# Video_critter_hires_v01.net
KiCad netlist of a schematic drawn in EAGLE
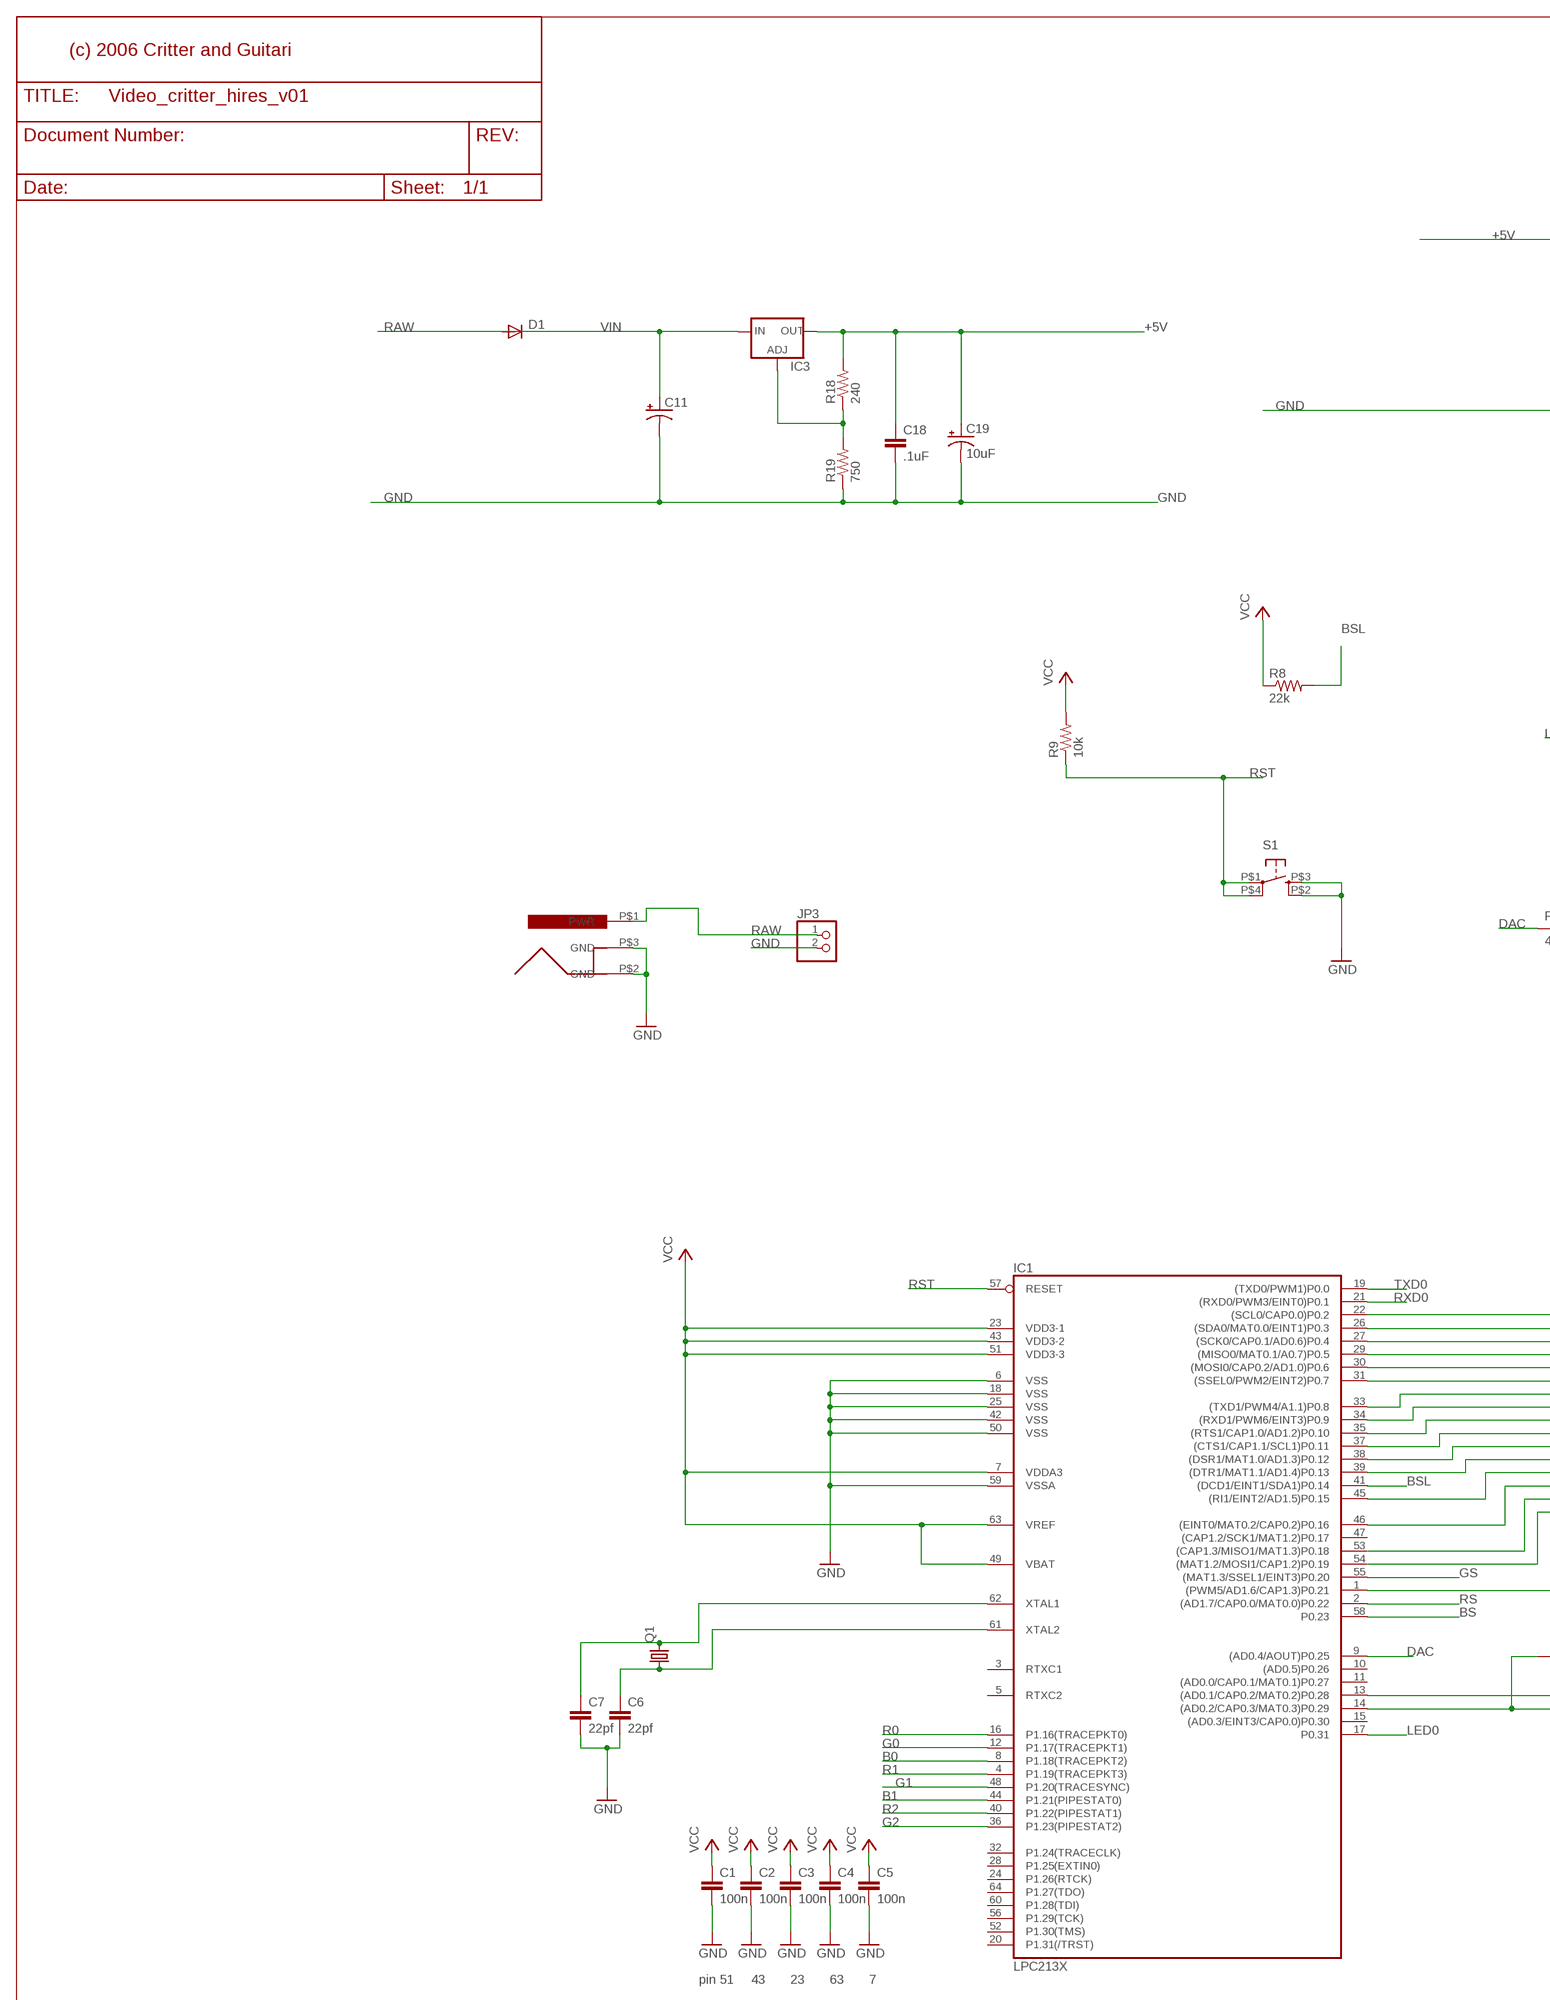
[diagram p0: schematic, sheet 1, part 1 of 2]
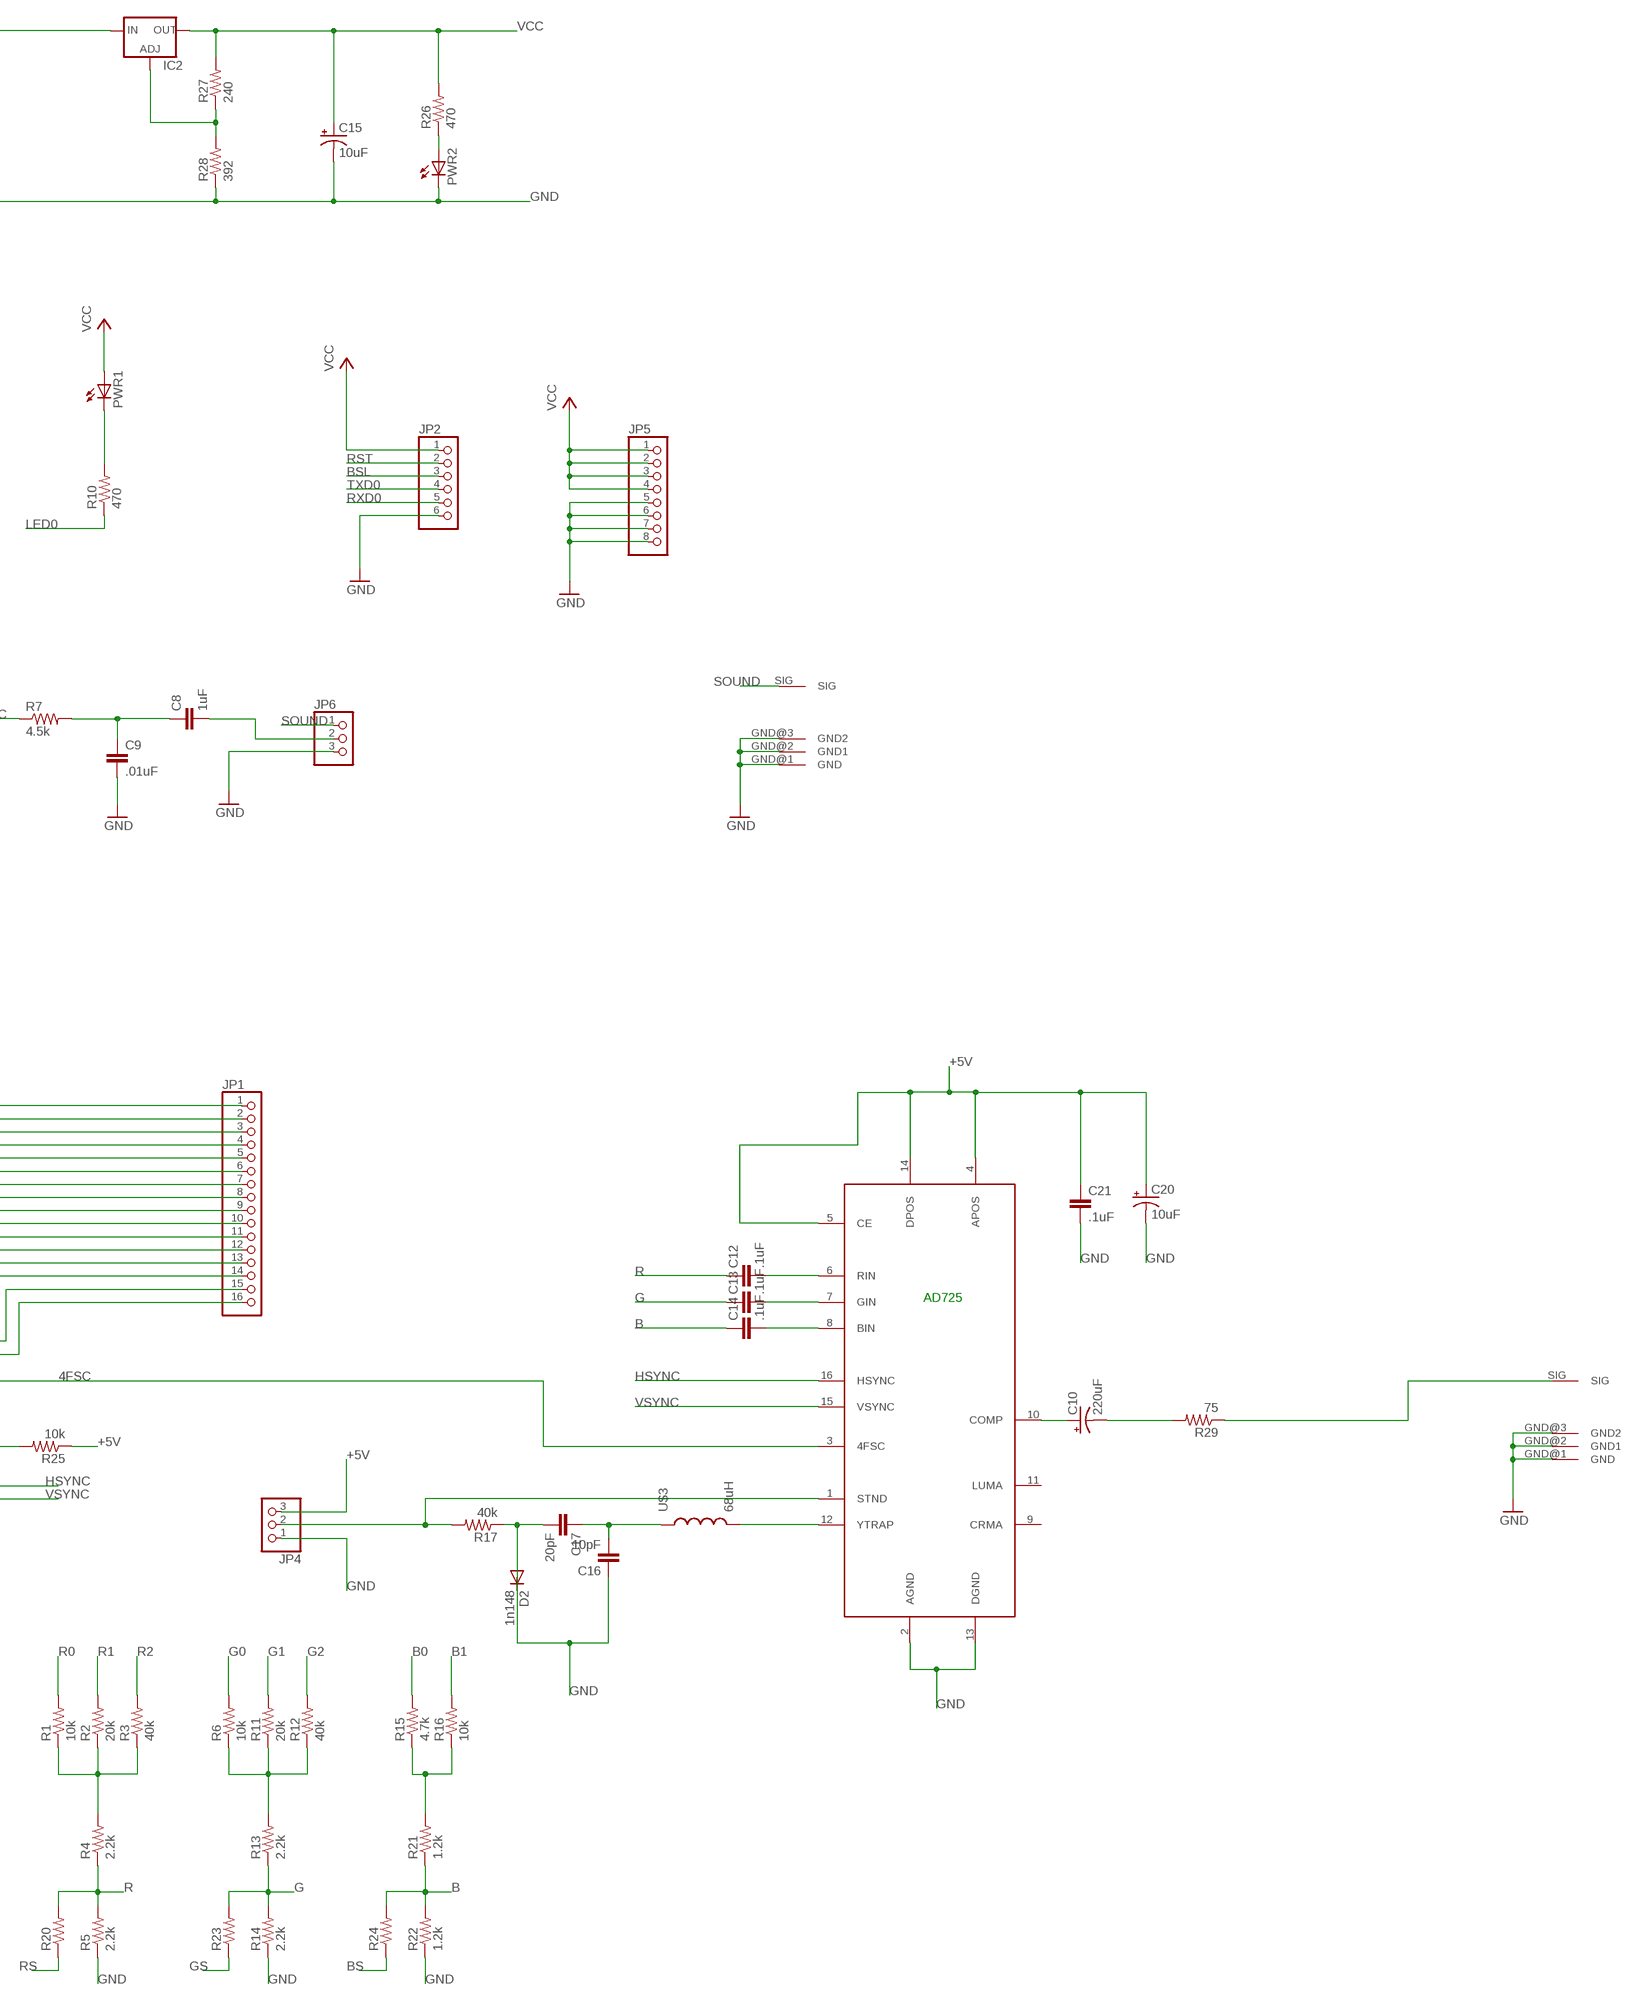
[diagram p1: schematic, sheet 1, part 2 of 2]

(export (version "E")
  (design (tool "Eeschema 10.0.6"))
  (components
    (comp (ref "C1")
      (value "100n")
      (footprint "eagle-import:C0603")
      (libsource (lib "eagle-import") (part "CAP0603"))
    )
    (comp (ref "C2")
      (value "100n")
      (footprint "eagle-import:C0603")
      (libsource (lib "eagle-import") (part "CAP0603"))
    )
    (comp (ref "C3")
      (value "100n")
      (footprint "eagle-import:C0603")
      (libsource (lib "eagle-import") (part "CAP0603"))
    )
    (comp (ref "C4")
      (value "100n")
      (footprint "eagle-import:C0603")
      (libsource (lib "eagle-import") (part "CAP0603"))
    )
    (comp (ref "C5")
      (value "100n")
      (footprint "eagle-import:C0603")
      (libsource (lib "eagle-import") (part "CAP0603"))
    )
    (comp (ref "C6")
      (value "22pf")
      (footprint "eagle-import:C0603")
      (libsource (lib "eagle-import") (part "CAP0603"))
    )
    (comp (ref "C7")
      (value "22pf")
      (footprint "eagle-import:C0603")
      (libsource (lib "eagle-import") (part "CAP0603"))
    )
    (comp (ref "C8")
      (value "1uF")
      (footprint "eagle-import:C0603")
      (libsource (lib "eagle-import") (part "CAP0603"))
    )
    (comp (ref "C9")
      (value ".01uF")
      (footprint "eagle-import:C0603")
      (libsource (lib "eagle-import") (part "CAP0603"))
    )
    (comp (ref "C10")
      (value "220uF")
      (footprint "eagle-import:PANASONIC_D")
      (libsource (lib "eagle-import") (part "CPOL-USD"))
    )
    (comp (ref "C11")
      (value "CPOL-USE3.5-8")
      (footprint "eagle-import:E3,5-8")
      (libsource (lib "eagle-import") (part "CPOL-USE3.5-8"))
    )
    (comp (ref "C12")
      (value ".1uF")
      (footprint "eagle-import:C0603")
      (libsource (lib "eagle-import") (part "CAP0603"))
    )
    (comp (ref "C13")
      (value ".1uF")
      (footprint "eagle-import:C0603")
      (libsource (lib "eagle-import") (part "CAP0603"))
    )
    (comp (ref "C14")
      (value ".1uF")
      (footprint "eagle-import:C0603")
      (libsource (lib "eagle-import") (part "CAP0603"))
    )
    (comp (ref "C15")
      (value "10uF")
      (footprint "eagle-import:CPOL_1206")
      (libsource (lib "eagle-import") (part "CAP_POL1206"))
    )
    (comp (ref "C16")
      (value "10pF")
      (footprint "eagle-import:C0603")
      (libsource (lib "eagle-import") (part "CAP0603"))
    )
    (comp (ref "C17")
      (value "20pF")
      (footprint "eagle-import:C0603")
      (libsource (lib "eagle-import") (part "CAP0603"))
    )
    (comp (ref "C18")
      (value ".1uF")
      (footprint "eagle-import:C0603")
      (libsource (lib "eagle-import") (part "CAP0603"))
    )
    (comp (ref "C19")
      (value "10uF")
      (footprint "eagle-import:CPOL_1206")
      (libsource (lib "eagle-import") (part "CAP_POL1206"))
    )
    (comp (ref "C20")
      (value "10uF")
      (footprint "eagle-import:CPOL_1206")
      (libsource (lib "eagle-import") (part "CAP_POL1206"))
    )
    (comp (ref "C21")
      (value ".1uF")
      (footprint "eagle-import:C0603")
      (libsource (lib "eagle-import") (part "CAP0603"))
    )
    (comp (ref "D1")
      (value "DIODESMB")
      (footprint "eagle-import:SMB")
      (libsource (lib "eagle-import") (part "DIODESMB"))
    )
    (comp (ref "D2")
      (value "1n148")
      (footprint "eagle-import:SOD323-W")
      (libsource (lib "eagle-import") (part "DIODE"))
    )
    (comp (ref "IC1")
      (value "LPC213X")
      (footprint "eagle-import:SQFP-S-10X10-64")
      (libsource (lib "eagle-import") (part "LPC213X"))
    )
    (comp (ref "IC2")
      (value "V_REG_FAN1117SOT223")
      (footprint "eagle-import:SOT223")
      (libsource (lib "eagle-import") (part "V_REG_FAN1117SOT223"))
    )
    (comp (ref "IC3")
      (value "V_REG_FAN1117SOT223")
      (footprint "eagle-import:SOT223")
      (libsource (lib "eagle-import") (part "V_REG_FAN1117SOT223"))
    )
    (comp (ref "JP1")
      (value "PINHD-1X16")
      (footprint "eagle-import:1X16")
      (libsource (lib "eagle-import") (part "PINHD-1X16"))
    )
    (comp (ref "JP2")
      (value "PINHD-1X6")
      (footprint "eagle-import:1X06")
      (libsource (lib "eagle-import") (part "PINHD-1X6"))
    )
    (comp (ref "JP3")
      (value "PINHD-1X2")
      (footprint "eagle-import:1X02")
      (libsource (lib "eagle-import") (part "PINHD-1X2"))
    )
    (comp (ref "JP4")
      (value "PINHD-1X3")
      (footprint "eagle-import:1X03")
      (libsource (lib "eagle-import") (part "PINHD-1X3"))
    )
    (comp (ref "JP5")
      (value "PINHD-1X8")
      (footprint "eagle-import:1X08")
      (libsource (lib "eagle-import") (part "PINHD-1X8"))
    )
    (comp (ref "JP6")
      (value "PINHD-1X3")
      (footprint "eagle-import:1X03")
      (libsource (lib "eagle-import") (part "PINHD-1X3"))
    )
    (comp (ref "PWR1")
      (value "LED1206")
      (footprint "eagle-import:CHIPLED_1206")
      (libsource (lib "eagle-import") (part "LED1206"))
    )
    (comp (ref "PWR2")
      (value "LED1206")
      (footprint "eagle-import:CHIPLED_1206")
      (libsource (lib "eagle-import") (part "LED1206"))
    )
    (comp (ref "Q1")
      (value "CRYSTALSOCKETED")
      (footprint "eagle-import:HC49U-SOCKETED")
      (libsource (lib "eagle-import") (part "CRYSTALSOCKETED"))
    )
    (comp (ref "R1")
      (value "10k")
      (footprint "eagle-import:R0603")
      (libsource (lib "eagle-import") (part "RES0603"))
    )
    (comp (ref "R2")
      (value "20k")
      (footprint "eagle-import:R0603")
      (libsource (lib "eagle-import") (part "RES0603"))
    )
    (comp (ref "R3")
      (value "40k")
      (footprint "eagle-import:R0603")
      (libsource (lib "eagle-import") (part "RES0603"))
    )
    (comp (ref "R4")
      (value "2.2k")
      (footprint "eagle-import:R0603")
      (libsource (lib "eagle-import") (part "RES0603"))
    )
    (comp (ref "R5")
      (value "2.2k")
      (footprint "eagle-import:R0603")
      (libsource (lib "eagle-import") (part "RES0603"))
    )
    (comp (ref "R6")
      (value "10k")
      (footprint "eagle-import:R0603")
      (libsource (lib "eagle-import") (part "RES0603"))
    )
    (comp (ref "R7")
      (value "4.5k")
      (footprint "eagle-import:R0603")
      (libsource (lib "eagle-import") (part "RES0603"))
    )
    (comp (ref "R8")
      (value "22k")
      (footprint "eagle-import:R0603")
      (libsource (lib "eagle-import") (part "RES0603"))
    )
    (comp (ref "R9")
      (value "10k")
      (footprint "eagle-import:R0603")
      (libsource (lib "eagle-import") (part "RES0603"))
    )
    (comp (ref "R10")
      (value "470")
      (footprint "eagle-import:R0603")
      (libsource (lib "eagle-import") (part "RES0603"))
    )
    (comp (ref "R11")
      (value "20k")
      (footprint "eagle-import:R0603")
      (libsource (lib "eagle-import") (part "RES0603"))
    )
    (comp (ref "R12")
      (value "40k")
      (footprint "eagle-import:R0603")
      (libsource (lib "eagle-import") (part "RES0603"))
    )
    (comp (ref "R13")
      (value "2.2k")
      (footprint "eagle-import:R0603")
      (libsource (lib "eagle-import") (part "RES0603"))
    )
    (comp (ref "R14")
      (value "2.2k")
      (footprint "eagle-import:R0603")
      (libsource (lib "eagle-import") (part "RES0603"))
    )
    (comp (ref "R15")
      (value "4.7k")
      (footprint "eagle-import:R0603")
      (libsource (lib "eagle-import") (part "RES0603"))
    )
    (comp (ref "R16")
      (value "10k")
      (footprint "eagle-import:R0603")
      (libsource (lib "eagle-import") (part "RES0603"))
    )
    (comp (ref "R17")
      (value "40k")
      (footprint "eagle-import:R0603")
      (libsource (lib "eagle-import") (part "RES0603"))
    )
    (comp (ref "R18")
      (value "240")
      (footprint "eagle-import:R0603")
      (libsource (lib "eagle-import") (part "RES0603"))
    )
    (comp (ref "R19")
      (value "750")
      (footprint "eagle-import:R0603")
      (libsource (lib "eagle-import") (part "RES0603"))
    )
    (comp (ref "R20")
      (value "RES0603")
      (footprint "eagle-import:R0603")
      (libsource (lib "eagle-import") (part "RES0603"))
    )
    (comp (ref "R21")
      (value "1.2k")
      (footprint "eagle-import:R0603")
      (libsource (lib "eagle-import") (part "RES0603"))
    )
    (comp (ref "R22")
      (value "1.2k")
      (footprint "eagle-import:R0603")
      (libsource (lib "eagle-import") (part "RES0603"))
    )
    (comp (ref "R23")
      (value "RES0603")
      (footprint "eagle-import:R0603")
      (libsource (lib "eagle-import") (part "RES0603"))
    )
    (comp (ref "R24")
      (value "RES0603")
      (footprint "eagle-import:R0603")
      (libsource (lib "eagle-import") (part "RES0603"))
    )
    (comp (ref "R25")
      (value "10k")
      (footprint "eagle-import:R0603")
      (libsource (lib "eagle-import") (part "RES0603"))
    )
    (comp (ref "R26")
      (value "470")
      (footprint "eagle-import:R0603")
      (libsource (lib "eagle-import") (part "RES0603"))
    )
    (comp (ref "R27")
      (value "240")
      (footprint "eagle-import:R0603")
      (libsource (lib "eagle-import") (part "RES0603"))
    )
    (comp (ref "R28")
      (value "392")
      (footprint "eagle-import:R0603")
      (libsource (lib "eagle-import") (part "RES0603"))
    )
    (comp (ref "R29")
      (value "75")
      (footprint "eagle-import:R0603")
      (libsource (lib "eagle-import") (part "RES0603"))
    )
    (comp (ref "S1")
      (value "TAC_SWITCH")
      (footprint "eagle-import:TACTILE_SWITCH_SMD")
      (libsource (lib "eagle-import") (part "TAC_SWITCH"))
    )
    (comp (ref "U$1")
      (value "POWER_JACK")
      (footprint "eagle-import:POWER_JACK")
      (libsource (lib "eagle-import") (part "POWER_JACKTHRU-HOLE"))
    )
    (comp (ref "U$2")
      (value "AD725")
      (footprint "eagle-import:SO16L")
      (libsource (lib "eagle-import") (part "AD725"))
    )
    (comp (ref "U$3")
      (value "68uH")
      (footprint "eagle-import:INDUCTOR_SMALL")
      (libsource (lib "eagle-import") (part "INDUCTORSMALL"))
    )
    (comp (ref "U$5")
      (value "PHONO_PLUG")
      (footprint "eagle-import:PHONO_PCB")
      (libsource (lib "eagle-import") (part "PHONO_PLUG"))
    )
    (comp (ref "U$7")
      (value "PHONO_PLUG")
      (footprint "eagle-import:PHONO_PCB")
      (libsource (lib "eagle-import") (part "PHONO_PLUG"))
    )
  )
  (nets
    (net (code "1") (name "/+5V") (class "Default")
      (node (ref "C18") (pin "1") (pinfunction "1_1") (pintype "passive"))
      (node (ref "C19") (pin "A") (pinfunction "+_A") (pintype "passive"))
      (node (ref "C20") (pin "A") (pinfunction "+_A") (pintype "passive"))
      (node (ref "C21") (pin "1") (pinfunction "1_1") (pintype "passive"))
      (node (ref "IC2") (pin "3") (pinfunction "IN_3") (pintype "input"))
      (node (ref "IC3") (pin "2") (pinfunction "OUT_2") (pintype "passive"))
      (node (ref "JP4") (pin "3") (pinfunction "3_3") (pintype "passive"))
      (node (ref "R18") (pin "2") (pinfunction "2_2") (pintype "passive"))
      (node (ref "R25") (pin "1") (pinfunction "1_1") (pintype "passive"))
      (node (ref "U$2") (pin "14") (pinfunction "DPOS_14") (pintype "bidirectional"))
      (node (ref "U$2") (pin "4") (pinfunction "APOS_4") (pintype "bidirectional"))
      (node (ref "U$2") (pin "5") (pinfunction "CE_5") (pintype "bidirectional"))
    )
    (net (code "2") (name "/4FSC") (class "Default")
      (node (ref "IC1") (pin "1") (pinfunction "(PWM5/AD1.6/CAP1.3)P0.21_1") (pintype "bidirectional"))
      (node (ref "U$2") (pin "3") (pinfunction "4FSC_3") (pintype "bidirectional"))
    )
    (net (code "3") (name "/B") (class "Default")
      (node (ref "C14") (pin "1") (pinfunction "1_1") (pintype "passive"))
      (node (ref "R21") (pin "1") (pinfunction "1_1") (pintype "passive"))
      (node (ref "R22") (pin "2") (pinfunction "2_2") (pintype "passive"))
      (node (ref "R24") (pin "2") (pinfunction "2_2") (pintype "passive"))
    )
    (net (code "4") (name "/B0") (class "Default")
      (node (ref "IC1") (pin "8") (pinfunction "P1.18(TRACEPKT2)_8") (pintype "bidirectional"))
      (node (ref "R15") (pin "2") (pinfunction "2_2") (pintype "passive"))
    )
    (net (code "5") (name "/B1") (class "Default")
      (node (ref "IC1") (pin "44") (pinfunction "P1.21(PIPESTAT0)_44") (pintype "bidirectional"))
      (node (ref "R16") (pin "2") (pinfunction "2_2") (pintype "passive"))
    )
    (net (code "6") (name "/BS") (class "Default")
      (node (ref "IC1") (pin "58") (pinfunction "P0.23_58") (pintype "bidirectional"))
      (node (ref "R24") (pin "1") (pinfunction "1_1") (pintype "passive"))
    )
    (net (code "7") (name "/BSL") (class "Default")
      (node (ref "IC1") (pin "41") (pinfunction "(DCD1/EINT1/SDA1)P0.14_41") (pintype "bidirectional"))
      (node (ref "JP2") (pin "3") (pinfunction "3_3") (pintype "passive"))
      (node (ref "R8") (pin "2") (pinfunction "2_2") (pintype "passive"))
    )
    (net (code "8") (name "/DAC") (class "Default")
      (node (ref "IC1") (pin "9") (pinfunction "(AD0.4/AOUT)P0.25_9") (pintype "bidirectional"))
      (node (ref "R7") (pin "1") (pinfunction "1_1") (pintype "passive"))
    )
    (net (code "9") (name "/G") (class "Default")
      (node (ref "C13") (pin "1") (pinfunction "1_1") (pintype "passive"))
      (node (ref "R13") (pin "1") (pinfunction "1_1") (pintype "passive"))
      (node (ref "R14") (pin "2") (pinfunction "2_2") (pintype "passive"))
      (node (ref "R23") (pin "2") (pinfunction "2_2") (pintype "passive"))
    )
    (net (code "10") (name "/G0") (class "Default")
      (node (ref "IC1") (pin "12") (pinfunction "P1.17(TRACEPKT1)_12") (pintype "bidirectional"))
      (node (ref "R6") (pin "2") (pinfunction "2_2") (pintype "passive"))
    )
    (net (code "11") (name "/G1") (class "Default")
      (node (ref "IC1") (pin "48") (pinfunction "P1.20(TRACESYNC)_48") (pintype "bidirectional"))
      (node (ref "R11") (pin "2") (pinfunction "2_2") (pintype "passive"))
    )
    (net (code "12") (name "/G2") (class "Default")
      (node (ref "IC1") (pin "36") (pinfunction "P1.23(PIPESTAT2)_36") (pintype "bidirectional"))
      (node (ref "R12") (pin "2") (pinfunction "2_2") (pintype "passive"))
    )
    (net (code "13") (name "/GS") (class "Default")
      (node (ref "IC1") (pin "55") (pinfunction "(MAT1.3/SSEL1/EINT3)P0.20_55") (pintype "bidirectional"))
      (node (ref "R23") (pin "1") (pinfunction "1_1") (pintype "passive"))
    )
    (net (code "14") (name "/HSYNC") (class "Default")
      (node (ref "IC1") (pin "13") (pinfunction "(AD0.1/CAP0.2/MAT0.2)P0.28_13") (pintype "bidirectional"))
      (node (ref "U$2") (pin "16") (pinfunction "HSYNC_16") (pintype "bidirectional"))
    )
    (net (code "15") (name "/LED0") (class "Default")
      (node (ref "IC1") (pin "17") (pinfunction "P0.31_17") (pintype "output"))
      (node (ref "R10") (pin "1") (pinfunction "1_1") (pintype "passive"))
    )
    (net (code "16") (name "/R") (class "Default")
      (node (ref "C12") (pin "1") (pinfunction "1_1") (pintype "passive"))
      (node (ref "R20") (pin "2") (pinfunction "2_2") (pintype "passive"))
      (node (ref "R4") (pin "1") (pinfunction "1_1") (pintype "passive"))
      (node (ref "R5") (pin "2") (pinfunction "2_2") (pintype "passive"))
    )
    (net (code "17") (name "/R0") (class "Default")
      (node (ref "IC1") (pin "16") (pinfunction "P1.16(TRACEPKT0)_16") (pintype "bidirectional"))
      (node (ref "R1") (pin "2") (pinfunction "2_2") (pintype "passive"))
    )
    (net (code "18") (name "/R1") (class "Default")
      (node (ref "IC1") (pin "4") (pinfunction "P1.19(TRACEPKT3)_4") (pintype "bidirectional"))
      (node (ref "R2") (pin "2") (pinfunction "2_2") (pintype "passive"))
    )
    (net (code "19") (name "/R2") (class "Default")
      (node (ref "IC1") (pin "40") (pinfunction "P1.22(PIPESTAT1)_40") (pintype "bidirectional"))
      (node (ref "R3") (pin "2") (pinfunction "2_2") (pintype "passive"))
    )
    (net (code "20") (name "/RAW") (class "Default")
      (node (ref "D1") (pin "1") (pinfunction "C_1") (pintype "passive"))
      (node (ref "JP3") (pin "1") (pinfunction "1_1") (pintype "passive"))
      (node (ref "U$1") (pin "P$1") (pinfunction "PWR_P$1") (pintype "bidirectional"))
    )
    (net (code "21") (name "/RS") (class "Default")
      (node (ref "IC1") (pin "2") (pinfunction "(AD1.7/CAP0.0/MAT0.0)P0.22_2") (pintype "bidirectional"))
      (node (ref "R20") (pin "1") (pinfunction "1_1") (pintype "passive"))
    )
    (net (code "22") (name "/RST") (class "Default")
      (node (ref "IC1") (pin "57") (pinfunction "RESET_57") (pintype "input"))
      (node (ref "JP2") (pin "2") (pinfunction "2_2") (pintype "passive"))
      (node (ref "R9") (pin "1") (pinfunction "1_1") (pintype "passive"))
      (node (ref "S1") (pin "P$1") (pinfunction "P_P$1") (pintype "passive"))
      (node (ref "S1") (pin "P$4") (pinfunction "P1_P$4") (pintype "passive"))
    )
    (net (code "23") (name "/RXD0") (class "Default")
      (node (ref "IC1") (pin "21") (pinfunction "(RXD0/PWM3/EINT0)P0.1_21") (pintype "bidirectional"))
      (node (ref "JP2") (pin "5") (pinfunction "5_5") (pintype "passive"))
    )
    (net (code "24") (name "/SOUND") (class "Default")
      (node (ref "JP6") (pin "1") (pinfunction "1_1") (pintype "passive"))
      (node (ref "U$5") (pin "SIG") (pinfunction "SIG_SIG") (pintype "bidirectional"))
    )
    (net (code "25") (name "/TXD0") (class "Default")
      (node (ref "IC1") (pin "19") (pinfunction "(TXD0/PWM1)P0.0_19") (pintype "bidirectional"))
      (node (ref "JP2") (pin "4") (pinfunction "4_4") (pintype "passive"))
    )
    (net (code "26") (name "/VIN") (class "Default")
      (node (ref "C11") (pin "+") (pinfunction "+_+") (pintype "passive"))
      (node (ref "D1") (pin "2") (pinfunction "A_2") (pintype "passive"))
      (node (ref "IC3") (pin "3") (pinfunction "IN_3") (pintype "input"))
    )
    (net (code "27") (name "/VSYNC") (class "Default")
      (node (ref "IC1") (pin "14") (pinfunction "(AD0.2/CAP0.3/MAT0.3)P0.29_14") (pintype "bidirectional"))
      (node (ref "R25") (pin "2") (pinfunction "2_2") (pintype "passive"))
      (node (ref "U$2") (pin "15") (pinfunction "VSYNC_15") (pintype "bidirectional"))
    )
    (net (code "28") (name "GND") (class "Default")
      (node (ref "C1") (pin "2") (pinfunction "2_2") (pintype "passive"))
      (node (ref "C11") (pin "-") (pinfunction "-_-") (pintype "passive"))
      (node (ref "C15") (pin "C") (pinfunction "-_C") (pintype "passive"))
      (node (ref "C16") (pin "1") (pinfunction "1_1") (pintype "passive"))
      (node (ref "C18") (pin "2") (pinfunction "2_2") (pintype "passive"))
      (node (ref "C19") (pin "C") (pinfunction "-_C") (pintype "passive"))
      (node (ref "C2") (pin "2") (pinfunction "2_2") (pintype "passive"))
      (node (ref "C20") (pin "C") (pinfunction "-_C") (pintype "passive"))
      (node (ref "C21") (pin "2") (pinfunction "2_2") (pintype "passive"))
      (node (ref "C3") (pin "2") (pinfunction "2_2") (pintype "passive"))
      (node (ref "C4") (pin "2") (pinfunction "2_2") (pintype "passive"))
      (node (ref "C5") (pin "2") (pinfunction "2_2") (pintype "passive"))
      (node (ref "C6") (pin "2") (pinfunction "2_2") (pintype "passive"))
      (node (ref "C7") (pin "2") (pinfunction "2_2") (pintype "passive"))
      (node (ref "C9") (pin "2") (pinfunction "2_2") (pintype "passive"))
      (node (ref "D2") (pin "A") (pinfunction "A_A") (pintype "passive"))
      (node (ref "IC1") (pin "18") (pinfunction "VSS_18") (pintype "power_in"))
      (node (ref "IC1") (pin "25") (pinfunction "VSS_25") (pintype "power_in"))
      (node (ref "IC1") (pin "42") (pinfunction "VSS_42") (pintype "power_in"))
      (node (ref "IC1") (pin "50") (pinfunction "VSS_50") (pintype "power_in"))
      (node (ref "IC1") (pin "59") (pinfunction "VSSA_59") (pintype "power_in"))
      (node (ref "IC1") (pin "6") (pinfunction "VSS_6") (pintype "power_in"))
      (node (ref "JP2") (pin "6") (pinfunction "6_6") (pintype "passive"))
      (node (ref "JP3") (pin "2") (pinfunction "2_2") (pintype "passive"))
      (node (ref "JP4") (pin "1") (pinfunction "1_1") (pintype "passive"))
      (node (ref "JP5") (pin "5") (pinfunction "5_5") (pintype "passive"))
      (node (ref "JP5") (pin "6") (pinfunction "6_6") (pintype "passive"))
      (node (ref "JP5") (pin "7") (pinfunction "7_7") (pintype "passive"))
      (node (ref "JP5") (pin "8") (pinfunction "8_8") (pintype "passive"))
      (node (ref "JP6") (pin "3") (pinfunction "3_3") (pintype "passive"))
      (node (ref "PWR2") (pin "C") (pinfunction "C_C") (pintype "passive"))
      (node (ref "R14") (pin "1") (pinfunction "1_1") (pintype "passive"))
      (node (ref "R19") (pin "1") (pinfunction "1_1") (pintype "passive"))
      (node (ref "R22") (pin "1") (pinfunction "1_1") (pintype "passive"))
      (node (ref "R28") (pin "1") (pinfunction "1_1") (pintype "passive"))
      (node (ref "R5") (pin "1") (pinfunction "1_1") (pintype "passive"))
      (node (ref "S1") (pin "P$2") (pinfunction "S1_P$2") (pintype "passive"))
      (node (ref "S1") (pin "P$3") (pinfunction "S_P$3") (pintype "passive"))
      (node (ref "U$1") (pin "P$2") (pinfunction "GND_P$2") (pintype "bidirectional"))
      (node (ref "U$1") (pin "P$3") (pinfunction "GND_P$3") (pintype "bidirectional"))
      (node (ref "U$2") (pin "13") (pinfunction "DGND_13") (pintype "bidirectional"))
      (node (ref "U$2") (pin "2") (pinfunction "AGND_2") (pintype "bidirectional"))
      (node (ref "U$5") (pin "GND@1") (pinfunction "GND_GND@1") (pintype "bidirectional"))
      (node (ref "U$5") (pin "GND@2") (pinfunction "GND1_GND@2") (pintype "bidirectional"))
      (node (ref "U$5") (pin "GND@3") (pinfunction "GND2_GND@3") (pintype "bidirectional"))
      (node (ref "U$7") (pin "GND@1") (pinfunction "GND_GND@1") (pintype "bidirectional"))
      (node (ref "U$7") (pin "GND@2") (pinfunction "GND1_GND@2") (pintype "bidirectional"))
      (node (ref "U$7") (pin "GND@3") (pinfunction "GND2_GND@3") (pintype "bidirectional"))
    )
    (net (code "29") (name "Net-(C8-Pad1)") (class "Default")
      (node (ref "C8") (pin "1") (pinfunction "1_1") (pintype "passive"))
      (node (ref "C9") (pin "1") (pinfunction "1_1") (pintype "passive"))
      (node (ref "R7") (pin "2") (pinfunction "2_2") (pintype "passive"))
    )
    (net (code "30") (name "Net-(C8-Pad2)") (class "Default")
      (node (ref "C8") (pin "2") (pinfunction "2_2") (pintype "passive"))
      (node (ref "JP6") (pin "2") (pinfunction "2_2") (pintype "passive"))
    )
    (net (code "31") (name "Net-(C10-Pad-)") (class "Default")
      (node (ref "C10") (pin "-") (pinfunction "-_-") (pintype "passive"))
      (node (ref "R29") (pin "2") (pinfunction "2_2") (pintype "passive"))
    )
    (net (code "32") (name "Net-(C17-Pad2)") (class "Default")
      (node (ref "C17") (pin "2") (pinfunction "2_2") (pintype "passive"))
      (node (ref "D2") (pin "C") (pinfunction "C_C") (pintype "passive"))
      (node (ref "R17") (pin "1") (pinfunction "1_1") (pintype "passive"))
    )
    (net (code "33") (name "Net-(IC1-(CAP1.3{slash}MISO1{slash}MAT1.3)P0.18)") (class "Default")
      (node (ref "IC1") (pin "53") (pinfunction "(CAP1.3/MISO1/MAT1.3)P0.18_53") (pintype "bidirectional"))
      (node (ref "JP1") (pin "15") (pinfunction "15_15") (pintype "passive"))
    )
    (net (code "34") (name "Net-(IC1-(CTS1{slash}CAP1.1{slash}SCL1)P0.11)") (class "Default")
      (node (ref "IC1") (pin "37") (pinfunction "(CTS1/CAP1.1/SCL1)P0.11_37") (pintype "bidirectional"))
      (node (ref "JP1") (pin "10") (pinfunction "10_10") (pintype "passive"))
    )
    (net (code "35") (name "Net-(IC1-(DSR1{slash}MAT1.0{slash}AD1.3)P0.12)") (class "Default")
      (node (ref "IC1") (pin "38") (pinfunction "(DSR1/MAT1.0/AD1.3)P0.12_38") (pintype "bidirectional"))
      (node (ref "JP1") (pin "11") (pinfunction "11_11") (pintype "passive"))
    )
    (net (code "36") (name "Net-(IC1-(DTR1{slash}MAT1.1{slash}AD1.4)P0.13)") (class "Default")
      (node (ref "IC1") (pin "39") (pinfunction "(DTR1/MAT1.1/AD1.4)P0.13_39") (pintype "bidirectional"))
      (node (ref "JP1") (pin "12") (pinfunction "12_12") (pintype "passive"))
    )
    (net (code "37") (name "Net-(IC1-(EINT0{slash}MAT0.2{slash}CAP0.2)P0.16)") (class "Default")
      (node (ref "IC1") (pin "46") (pinfunction "(EINT0/MAT0.2/CAP0.2)P0.16_46") (pintype "bidirectional"))
      (node (ref "JP1") (pin "14") (pinfunction "14_14") (pintype "passive"))
    )
    (net (code "38") (name "Net-(IC1-(MAT1.2{slash}MOSI1{slash}CAP1.2)P0.19)") (class "Default")
      (node (ref "IC1") (pin "54") (pinfunction "(MAT1.2/MOSI1/CAP1.2)P0.19_54") (pintype "bidirectional"))
      (node (ref "JP1") (pin "16") (pinfunction "16_16") (pintype "passive"))
    )
    (net (code "39") (name "Net-(IC1-(MISO0{slash}MAT0.1{slash}A0.7)P0.5)") (class "Default")
      (node (ref "IC1") (pin "29") (pinfunction "(MISO0/MAT0.1/A0.7)P0.5_29") (pintype "bidirectional"))
      (node (ref "JP1") (pin "4") (pinfunction "4_4") (pintype "passive"))
    )
    (net (code "40") (name "Net-(IC1-(MOSI0{slash}CAP0.2{slash}AD1.0)P0.6)") (class "Default")
      (node (ref "IC1") (pin "30") (pinfunction "(MOSI0/CAP0.2/AD1.0)P0.6_30") (pintype "bidirectional"))
      (node (ref "JP1") (pin "5") (pinfunction "5_5") (pintype "passive"))
    )
    (net (code "41") (name "Net-(IC1-(RI1{slash}EINT2{slash}AD1.5)P0.15)") (class "Default")
      (node (ref "IC1") (pin "45") (pinfunction "(RI1/EINT2/AD1.5)P0.15_45") (pintype "bidirectional"))
      (node (ref "JP1") (pin "13") (pinfunction "13_13") (pintype "passive"))
    )
    (net (code "42") (name "Net-(IC1-(RTS1{slash}CAP1.0{slash}AD1.2)P0.10)") (class "Default")
      (node (ref "IC1") (pin "35") (pinfunction "(RTS1/CAP1.0/AD1.2)P0.10_35") (pintype "bidirectional"))
      (node (ref "JP1") (pin "9") (pinfunction "9_9") (pintype "passive"))
    )
    (net (code "43") (name "Net-(IC1-(RXD1{slash}PWM6{slash}EINT3)P0.9)") (class "Default")
      (node (ref "IC1") (pin "34") (pinfunction "(RXD1/PWM6/EINT3)P0.9_34") (pintype "bidirectional"))
      (node (ref "JP1") (pin "8") (pinfunction "8_8") (pintype "passive"))
    )
    (net (code "44") (name "Net-(IC1-(SCK0{slash}CAP0.1{slash}AD0.6)P0.4)") (class "Default")
      (node (ref "IC1") (pin "27") (pinfunction "(SCK0/CAP0.1/AD0.6)P0.4_27") (pintype "bidirectional"))
      (node (ref "JP1") (pin "3") (pinfunction "3_3") (pintype "passive"))
    )
    (net (code "45") (name "Net-(IC1-(SCL0{slash}CAP0.0)P0.2)") (class "Default")
      (node (ref "IC1") (pin "22") (pinfunction "(SCL0/CAP0.0)P0.2_22") (pintype "bidirectional"))
      (node (ref "JP1") (pin "1") (pinfunction "1_1") (pintype "passive"))
    )
    (net (code "46") (name "Net-(IC1-(SDA0{slash}MAT0.0{slash}EINT1)P0.3)") (class "Default")
      (node (ref "IC1") (pin "26") (pinfunction "(SDA0/MAT0.0/EINT1)P0.3_26") (pintype "bidirectional"))
      (node (ref "JP1") (pin "2") (pinfunction "2_2") (pintype "passive"))
    )
    (net (code "47") (name "Net-(IC1-(SSEL0{slash}PWM2{slash}EINT2)P0.7)") (class "Default")
      (node (ref "IC1") (pin "31") (pinfunction "(SSEL0/PWM2/EINT2)P0.7_31") (pintype "bidirectional"))
      (node (ref "JP1") (pin "6") (pinfunction "6_6") (pintype "passive"))
    )
    (net (code "48") (name "Net-(IC1-(TXD1{slash}PWM4{slash}A1.1)P0.8)") (class "Default")
      (node (ref "IC1") (pin "33") (pinfunction "(TXD1/PWM4/A1.1)P0.8_33") (pintype "bidirectional"))
      (node (ref "JP1") (pin "7") (pinfunction "7_7") (pintype "passive"))
    )
    (net (code "49") (name "Net-(IC1-XTAL1)") (class "Default")
      (node (ref "C7") (pin "1") (pinfunction "1_1") (pintype "passive"))
      (node (ref "IC1") (pin "62") (pinfunction "XTAL1_62") (pintype "input"))
      (node (ref "Q1") (pin "2") (pinfunction "2_2") (pintype "passive"))
    )
    (net (code "50") (name "Net-(IC1-XTAL2)") (class "Default")
      (node (ref "C6") (pin "1") (pinfunction "1_1") (pintype "passive"))
      (node (ref "IC1") (pin "61") (pinfunction "XTAL2_61") (pintype "output"))
      (node (ref "Q1") (pin "1") (pinfunction "1_1") (pintype "passive"))
    )
    (net (code "51") (name "Net-(IC2-ADJ)") (class "Default")
      (node (ref "IC2") (pin "1") (pinfunction "ADJ_1") (pintype "input"))
      (node (ref "R27") (pin "1") (pinfunction "1_1") (pintype "passive"))
      (node (ref "R28") (pin "2") (pinfunction "2_2") (pintype "passive"))
    )
    (net (code "52") (name "Net-(IC3-ADJ)") (class "Default")
      (node (ref "IC3") (pin "1") (pinfunction "ADJ_1") (pintype "input"))
      (node (ref "R18") (pin "1") (pinfunction "1_1") (pintype "passive"))
      (node (ref "R19") (pin "2") (pinfunction "2_2") (pintype "passive"))
    )
    (net (code "53") (name "Net-(PWR1-PadC)") (class "Default")
      (node (ref "PWR1") (pin "C") (pinfunction "C_C") (pintype "passive"))
      (node (ref "R10") (pin "2") (pinfunction "2_2") (pintype "passive"))
    )
    (net (code "54") (name "Net-(PWR2-PadA)") (class "Default")
      (node (ref "PWR2") (pin "A") (pinfunction "A_A") (pintype "passive"))
      (node (ref "R26") (pin "1") (pinfunction "1_1") (pintype "passive"))
    )
    (net (code "55") (name "Net-(R1-Pad1)") (class "Default")
      (node (ref "R1") (pin "1") (pinfunction "1_1") (pintype "passive"))
      (node (ref "R2") (pin "1") (pinfunction "1_1") (pintype "passive"))
      (node (ref "R3") (pin "1") (pinfunction "1_1") (pintype "passive"))
      (node (ref "R4") (pin "2") (pinfunction "2_2") (pintype "passive"))
    )
    (net (code "56") (name "Net-(R11-Pad1)") (class "Default")
      (node (ref "R11") (pin "1") (pinfunction "1_1") (pintype "passive"))
      (node (ref "R12") (pin "1") (pinfunction "1_1") (pintype "passive"))
      (node (ref "R13") (pin "2") (pinfunction "2_2") (pintype "passive"))
      (node (ref "R6") (pin "1") (pinfunction "1_1") (pintype "passive"))
    )
    (net (code "57") (name "Net-(R15-Pad1)") (class "Default")
      (node (ref "R15") (pin "1") (pinfunction "1_1") (pintype "passive"))
      (node (ref "R16") (pin "1") (pinfunction "1_1") (pintype "passive"))
      (node (ref "R21") (pin "2") (pinfunction "2_2") (pintype "passive"))
    )
    (net (code "58") (name "Net-(R29-Pad1)") (class "Default")
      (node (ref "R29") (pin "1") (pinfunction "1_1") (pintype "passive"))
      (node (ref "U$7") (pin "SIG") (pinfunction "SIG_SIG") (pintype "bidirectional"))
    )
    (net (code "59") (name "Net-(U$2-BIN)") (class "Default")
      (node (ref "C14") (pin "2") (pinfunction "2_2") (pintype "passive"))
      (node (ref "U$2") (pin "8") (pinfunction "BIN_8") (pintype "bidirectional"))
    )
    (net (code "60") (name "Net-(U$2-COMP)") (class "Default")
      (node (ref "C10") (pin "+") (pinfunction "+_+") (pintype "passive"))
      (node (ref "U$2") (pin "10") (pinfunction "COMP_10") (pintype "bidirectional"))
    )
    (net (code "61") (name "Net-(U$2-GIN)") (class "Default")
      (node (ref "C13") (pin "2") (pinfunction "2_2") (pintype "passive"))
      (node (ref "U$2") (pin "7") (pinfunction "GIN_7") (pintype "bidirectional"))
    )
    (net (code "62") (name "Net-(U$2-RIN)") (class "Default")
      (node (ref "C12") (pin "2") (pinfunction "2_2") (pintype "passive"))
      (node (ref "U$2") (pin "6") (pinfunction "RIN_6") (pintype "bidirectional"))
    )
    (net (code "63") (name "Net-(U$2-STND)") (class "Default")
      (node (ref "JP4") (pin "2") (pinfunction "2_2") (pintype "passive"))
      (node (ref "R17") (pin "2") (pinfunction "2_2") (pintype "passive"))
      (node (ref "U$2") (pin "1") (pinfunction "STND_1") (pintype "bidirectional"))
    )
    (net (code "64") (name "Net-(U$2-YTRAP)") (class "Default")
      (node (ref "U$2") (pin "12") (pinfunction "YTRAP_12") (pintype "bidirectional"))
      (node (ref "U$3") (pin "P$2") (pinfunction "2_P$2") (pintype "passive"))
    )
    (net (code "65") (name "Net-(U$3-1)") (class "Default")
      (node (ref "C16") (pin "2") (pinfunction "2_2") (pintype "passive"))
      (node (ref "C17") (pin "1") (pinfunction "1_1") (pintype "passive"))
      (node (ref "U$3") (pin "P$1") (pinfunction "1_P$1") (pintype "passive"))
    )
    (net (code "66") (name "VCC") (class "Default")
      (node (ref "C1") (pin "1") (pinfunction "1_1") (pintype "passive"))
      (node (ref "C15") (pin "A") (pinfunction "+_A") (pintype "passive"))
      (node (ref "C2") (pin "1") (pinfunction "1_1") (pintype "passive"))
      (node (ref "C3") (pin "1") (pinfunction "1_1") (pintype "passive"))
      (node (ref "C4") (pin "1") (pinfunction "1_1") (pintype "passive"))
      (node (ref "C5") (pin "1") (pinfunction "1_1") (pintype "passive"))
      (node (ref "IC1") (pin "23") (pinfunction "VDD3-1_23") (pintype "power_in"))
      (node (ref "IC1") (pin "43") (pinfunction "VDD3-2_43") (pintype "power_in"))
      (node (ref "IC1") (pin "49") (pinfunction "VBAT_49") (pintype "power_in"))
      (node (ref "IC1") (pin "51") (pinfunction "VDD3-3_51") (pintype "power_in"))
      (node (ref "IC1") (pin "63") (pinfunction "VREF_63") (pintype "input"))
      (node (ref "IC1") (pin "7") (pinfunction "VDDA3_7") (pintype "power_in"))
      (node (ref "IC2") (pin "2") (pinfunction "OUT_2") (pintype "passive"))
      (node (ref "JP2") (pin "1") (pinfunction "1_1") (pintype "passive"))
      (node (ref "JP5") (pin "1") (pinfunction "1_1") (pintype "passive"))
      (node (ref "JP5") (pin "2") (pinfunction "2_2") (pintype "passive"))
      (node (ref "JP5") (pin "3") (pinfunction "3_3") (pintype "passive"))
      (node (ref "JP5") (pin "4") (pinfunction "4_4") (pintype "passive"))
      (node (ref "PWR1") (pin "A") (pinfunction "A_A") (pintype "passive"))
      (node (ref "R26") (pin "2") (pinfunction "2_2") (pintype "passive"))
      (node (ref "R27") (pin "2") (pinfunction "2_2") (pintype "passive"))
      (node (ref "R8") (pin "1") (pinfunction "1_1") (pintype "passive"))
      (node (ref "R9") (pin "2") (pinfunction "2_2") (pintype "passive"))
    )
    (net (code "67") (name "unconnected-(IC1-(AD0.0{slash}CAP0.1{slash}MAT0.1)P0.27-Pad11)") (class "Default")
      (node (ref "IC1") (pin "11") (pinfunction "(AD0.0/CAP0.1/MAT0.1)P0.27_11") (pintype "bidirectional"))
    )
    (net (code "68") (name "unconnected-(IC1-(AD0.3{slash}EINT3{slash}CAP0.0)P0.30-Pad15)") (class "Default")
      (node (ref "IC1") (pin "15") (pinfunction "(AD0.3/EINT3/CAP0.0)P0.30_15") (pintype "bidirectional"))
    )
    (net (code "69") (name "unconnected-(IC1-(AD0.5)P0.26-Pad10)") (class "Default")
      (node (ref "IC1") (pin "10") (pinfunction "(AD0.5)P0.26_10") (pintype "bidirectional"))
    )
    (net (code "70") (name "unconnected-(IC1-(CAP1.2{slash}SCK1{slash}MAT1.2)P0.17-Pad47)") (class "Default")
      (node (ref "IC1") (pin "47") (pinfunction "(CAP1.2/SCK1/MAT1.2)P0.17_47") (pintype "bidirectional"))
    )
    (net (code "71") (name "unconnected-(IC1-P1.24(TRACECLK)-Pad32)") (class "Default")
      (node (ref "IC1") (pin "32") (pinfunction "P1.24(TRACECLK)_32") (pintype "bidirectional"))
    )
    (net (code "72") (name "unconnected-(IC1-P1.25(EXTIN0)-Pad28)") (class "Default")
      (node (ref "IC1") (pin "28") (pinfunction "P1.25(EXTIN0)_28") (pintype "bidirectional"))
    )
    (net (code "73") (name "unconnected-(IC1-P1.26(RTCK)-Pad24)") (class "Default")
      (node (ref "IC1") (pin "24") (pinfunction "P1.26(RTCK)_24") (pintype "bidirectional"))
    )
    (net (code "74") (name "unconnected-(IC1-P1.27(TDO)-Pad64)") (class "Default")
      (node (ref "IC1") (pin "64") (pinfunction "P1.27(TDO)_64") (pintype "bidirectional"))
    )
    (net (code "75") (name "unconnected-(IC1-P1.28(TDI)-Pad60)") (class "Default")
      (node (ref "IC1") (pin "60") (pinfunction "P1.28(TDI)_60") (pintype "bidirectional"))
    )
    (net (code "76") (name "unconnected-(IC1-P1.29(TCK)-Pad56)") (class "Default")
      (node (ref "IC1") (pin "56") (pinfunction "P1.29(TCK)_56") (pintype "bidirectional"))
    )
    (net (code "77") (name "unconnected-(IC1-P1.30(TMS)-Pad52)") (class "Default")
      (node (ref "IC1") (pin "52") (pinfunction "P1.30(TMS)_52") (pintype "bidirectional"))
    )
    (net (code "78") (name "unconnected-(IC1-P1.31({slash}TRST)-Pad20)") (class "Default")
      (node (ref "IC1") (pin "20") (pinfunction "P1.31(/TRST)_20") (pintype "bidirectional"))
    )
    (net (code "79") (name "unconnected-(IC1-RTXC1-Pad3)") (class "Default")
      (node (ref "IC1") (pin "3") (pinfunction "RTXC1_3") (pintype "input"))
    )
    (net (code "80") (name "unconnected-(IC1-RTXC2-Pad5)") (class "Default")
      (node (ref "IC1") (pin "5") (pinfunction "RTXC2_5") (pintype "output"))
    )
    (net (code "81") (name "unconnected-(U$2-CRMA-Pad9)") (class "Default")
      (node (ref "U$2") (pin "9") (pinfunction "CRMA_9") (pintype "bidirectional"))
    )
    (net (code "82") (name "unconnected-(U$2-LUMA-Pad11)") (class "Default")
      (node (ref "U$2") (pin "11") (pinfunction "LUMA_11") (pintype "bidirectional"))
    )
  )
)
